# HIVE_SIGHT_POWER.net
KiCad netlist of a schematic drawn in Altium Designer
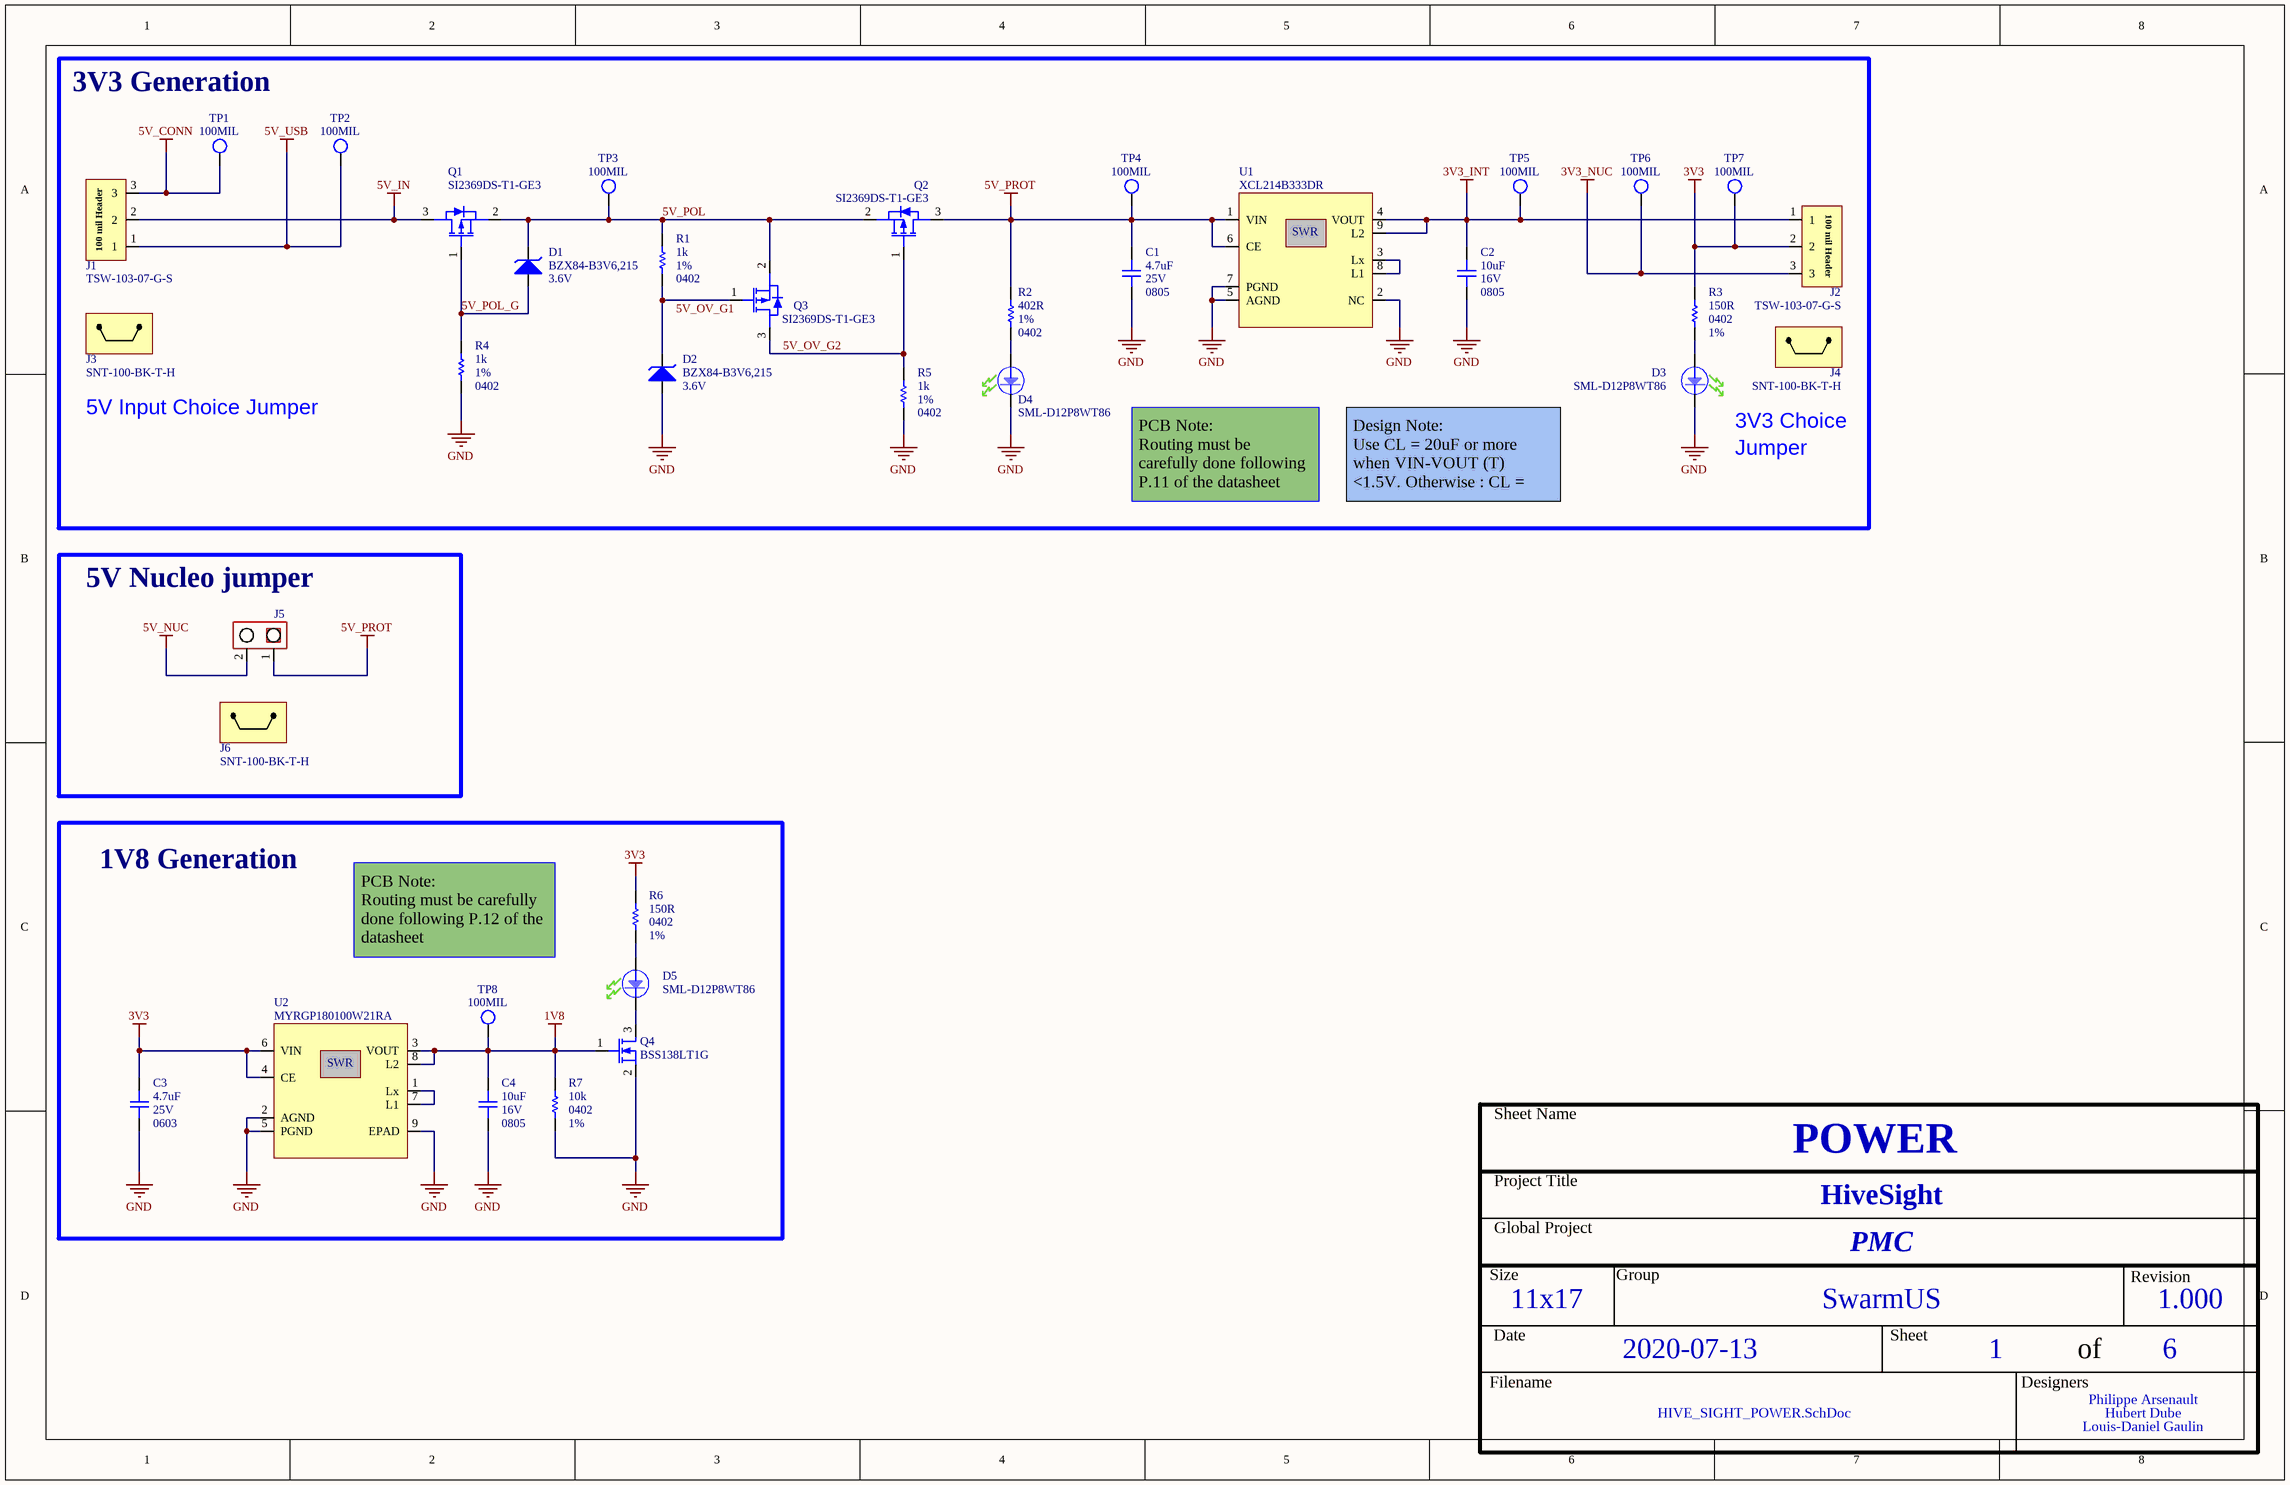
[diagram p0: HIVE_SIGHT_POWER.SchDoc]

(export (version "E")
  (design (tool "Eeschema 10.0.6"))
  (components
    (comp (ref "C1")
      (value "4.7uF")
      (footprint "CAP_CER_0805")
      (description "CAP - CER 4.7UF 10% 25V X7R - 0805")
      (fields
        (field (name "TOLERANCE") "10%")
        (field (name "PACKAGE") "0805")
        (field (name "VOLTAGE RATING") "25V")
        (field (name "Comment") "C2012X7R1E475K125AE")
        (field (name "CREATEDBY/DATE") "Keven Deslandes - 2018/11/09")
        (field (name "VERIFIEDBY") "Nicolas Roy - 2018/12/11")
      )
      (libsource (lib "GRAMS_MASTER_LIB") (part "CAP_CER_C2012X7R1E475K125AE"))
    )
    (comp (ref "C2")
      (value "10uF")
      (footprint "CAP_CER_0805")
      (description "CAP - CER 10UF 10% 16V X5R - 0805")
      (fields
        (field (name "TOLERANCE") "10%")
        (field (name "PACKAGE") "0805")
        (field (name "VOLTAGE RATING") "16V")
        (field (name "Comment") "GRM21BR61C106KE15K")
        (field (name "CREATEDBY/DATE") "Caroline Paulin / 8 août 2018")
        (field (name "VERIFIEDBY") "Nicolas V. (2019-01-22)")
      )
      (libsource (lib "GRAMS_MASTER_LIB") (part "CAP_CER_GRM21BR61C106KE15K"))
    )
    (comp (ref "C3")
      (value "4.7uF")
      (footprint "CAP_CER_0603")
      (description "CAP - CER 4.7µF 20% 25V X5R - 0603")
      (fields
        (field (name "TOLERANCE") "20%")
        (field (name "PACKAGE") "0603")
        (field (name "VOLTAGE RATING") "25V")
        (field (name "Comment") "CL10A475MA8NQNC")
        (field (name "CREATEDBY/DATE") "Nicolas Roy 2018-11-21")
        (field (name "VERIFIEDBY") "Nicolas V. (2019-01-22)")
      )
      (libsource (lib "GRAMS_MASTER_LIB") (part "CAP_CER_CL10A475MA8NQNC"))
    )
    (comp (ref "C4")
      (value "10uF")
      (footprint "CAP_CER_0805")
      (description "CAP - CER 10UF 10% 16V X5R - 0805")
      (fields
        (field (name "TOLERANCE") "10%")
        (field (name "PACKAGE") "0805")
        (field (name "VOLTAGE RATING") "16V")
        (field (name "Comment") "GRM21BR61C106KE15K")
        (field (name "CREATEDBY/DATE") "Caroline Paulin / 8 août 2018")
        (field (name "VERIFIEDBY") "Nicolas V. (2019-01-22)")
      )
      (libsource (lib "GRAMS_MASTER_LIB") (part "CAP_CER_GRM21BR61C106KE15K"))
    )
    (comp (ref "D1")
      (value "BZX84-B3V6,215")
      (footprint "DIO_ZENER_BZX84-B3V6,215")
      (description "DIO - ZENER 3.6V 250mW - SOT-23")
      (fields
        (field (name "TOLERANCE") "2%")
        (field (name "ALTIUM_VALUE") "3.6V")
        (field (name "CREATEDBY/DATE") "Louis-Daniel Gaulin / 30-07-2020")
        (field (name "VERIFIEDBY") "Philippe Arsenault/2020-11-06")
      )
      (libsource (lib "SWARMUS_LIB") (part "DIO_ZENER_BZX84-B3V6,215"))
    )
    (comp (ref "D2")
      (value "BZX84-B3V6,215")
      (footprint "DIO_ZENER_BZX84-B3V6,215")
      (description "DIO - ZENER 3.6V 250mW - SOT-23")
      (fields
        (field (name "TOLERANCE") "2%")
        (field (name "ALTIUM_VALUE") "3.6V")
        (field (name "CREATEDBY/DATE") "Louis-Daniel Gaulin / 30-07-2020")
        (field (name "VERIFIEDBY") "Philippe Arsenault/2020-11-06")
      )
      (libsource (lib "SWARMUS_LIB") (part "DIO_ZENER_BZX84-B3V6,215"))
    )
    (comp (ref "D3")
      (value "SML-D12P8WT86")
      (footprint "GRAMS_MASTER_LIB_PCB:LED_SML-D12P8WT86")
      (description "LED - GREEN DIFFUSED 0603 SMD - 0603")
      (fields
        (field (name "CREATEDBY/DATE") "Keven Deslandes - 2018/11/21")
        (field (name "VERIFIEDBY") "Caroline Paulin - 13 février 2019")
      )
      (libsource (lib "GRAMS_MASTER_LIB_SCH") (part "LED_SML-D12P8WT86"))
    )
    (comp (ref "D4")
      (value "SML-D12P8WT86")
      (footprint "GRAMS_MASTER_LIB_PCB:LED_SML-D12P8WT86")
      (description "LED - GREEN DIFFUSED 0603 SMD - 0603")
      (fields
        (field (name "CREATEDBY/DATE") "Keven Deslandes - 2018/11/21")
        (field (name "VERIFIEDBY") "Caroline Paulin - 13 février 2019")
      )
      (libsource (lib "GRAMS_MASTER_LIB_SCH") (part "LED_SML-D12P8WT86"))
    )
    (comp (ref "D5")
      (value "SML-D12P8WT86")
      (footprint "GRAMS_MASTER_LIB_PCB:LED_SML-D12P8WT86")
      (description "LED - GREEN DIFFUSED 0603 SMD - 0603")
      (fields
        (field (name "CREATEDBY/DATE") "Keven Deslandes - 2018/11/21")
        (field (name "VERIFIEDBY") "Caroline Paulin - 13 février 2019")
      )
      (libsource (lib "GRAMS_MASTER_LIB_SCH") (part "LED_SML-D12P8WT86"))
    )
    (comp (ref "J1")
      (value "TSW-103-07-G-S")
      (footprint "CON_HDR_TSW-103-07-G-S")
      (description "CON - HDR 100 MIL 3 POS - TH")
      (fields
        (field (name "CREATEDBY/DATE") "Jonathan Bouchard")
        (field (name "VERIFIEDBY") "Arnaud Samson 16-07-18")
      )
      (libsource (lib "") (part "CON_HDR_TSW-103-07-G-S_1"))
    )
    (comp (ref "J2")
      (value "TSW-103-07-G-S")
      (footprint "CON_HDR_TSW-103-07-G-S")
      (description "CON - HDR 100 MIL 3 POS - TH")
      (fields
        (field (name "CREATEDBY/DATE") "Jonathan Bouchard")
        (field (name "VERIFIEDBY") "Arnaud Samson 16-07-18")
      )
      (libsource (lib "GRAMS_MASTER_LIB") (part "CON_HDR_TSW-103-07-G-S"))
    )
    (comp (ref "J3")
      (value "SNT-100-BK-T-H")
      (footprint "CON_JMP_SNT-100-BK-T-H")
      (description "CON - CONN SHUNT - MEC")
      (fields
        (field (name "CREATEDBY/DATE") "Arnaud Samson - 09/07/18")
        (field (name "VERIFIEDBY") "Jonathan Bouchard 2018-07-12")
      )
      (libsource (lib "GRAMS_MASTER_LIB") (part "CON_JMP_SNT-100-BK-T-H"))
    )
    (comp (ref "J4")
      (value "SNT-100-BK-T-H")
      (footprint "CON_JMP_SNT-100-BK-T-H")
      (description "CON - CONN SHUNT - MEC")
      (fields
        (field (name "CREATEDBY/DATE") "Arnaud Samson - 09/07/18")
        (field (name "VERIFIEDBY") "Jonathan Bouchard 2018-07-12")
      )
      (libsource (lib "GRAMS_MASTER_LIB") (part "CON_JMP_SNT-100-BK-T-H"))
    )
    (comp (ref "J5")
      (value "CON_HDR_1x2")
      (footprint "CON_HDR_1X2")
      (description "CON - Header 1x2 pins 100 mil -TH")
      (fields
        (field (name "CREATEDBY/DATE") "Nicolas Roy/2 dec 2016")
        (field (name "VERIFIEDBY") "Caroline Paulin / 10 juillet 2018")
      )
      (libsource (lib "GRAMS_MASTER_LIB") (part "CON_HDR_1X2"))
    )
    (comp (ref "J6")
      (value "SNT-100-BK-T-H")
      (footprint "CON_JMP_SNT-100-BK-T-H")
      (description "CON - CONN SHUNT - MEC")
      (fields
        (field (name "CREATEDBY/DATE") "Arnaud Samson - 09/07/18")
        (field (name "VERIFIEDBY") "Jonathan Bouchard 2018-07-12")
      )
      (libsource (lib "GRAMS_MASTER_LIB") (part "CON_JMP_SNT-100-BK-T-H"))
    )
    (comp (ref "Q1")
      (value "SI2369DS-T1-GE3")
      (footprint "TRX_PMOS_SI2369DS-T1-GE3")
      (description "TRX - PMOS 30V 7.6A - SOT−23")
      (fields
        (field (name "CREATEDBY/DATE") "Louis-Daniel Gaulin / 30-07-2020")
        (field (name "VERIFIEDBY") "Philippe Arsenault/2020-11-06")
      )
      (libsource (lib "SWARMUS_LIB") (part "TRX_PMOS_SI2369DS-T1-GE3"))
    )
    (comp (ref "Q2")
      (value "SI2369DS-T1-GE3")
      (footprint "TRX_PMOS_SI2369DS-T1-GE3")
      (description "TRX - PMOS 30V 7.6A - SOT−23")
      (fields
        (field (name "CREATEDBY/DATE") "Louis-Daniel Gaulin / 30-07-2020")
        (field (name "VERIFIEDBY") "Philippe Arsenault/2020-11-06")
      )
      (libsource (lib "SWARMUS_LIB") (part "TRX_PMOS_SI2369DS-T1-GE3"))
    )
    (comp (ref "Q3")
      (value "SI2369DS-T1-GE3")
      (footprint "TRX_PMOS_SI2369DS-T1-GE3")
      (description "TRX - PMOS 30V 7.6A - SOT−23")
      (fields
        (field (name "CREATEDBY/DATE") "Louis-Daniel Gaulin / 30-07-2020")
        (field (name "VERIFIEDBY") "Philippe Arsenault/2020-11-06")
      )
      (libsource (lib "SWARMUS_LIB") (part "TRX_PMOS_SI2369DS-T1-GE3"))
    )
    (comp (ref "Q4")
      (value "BSS138LT1G")
      (footprint "TRX_NMOS_BSS138LT1G")
      (description "TRX - NMOS - 50V 200MA - SOT−23-3")
      (fields
        (field (name "CREATEDBY/DATE") "Joel Lemay 2018-06-15")
        (field (name "VERIFIEDBY") "Caroline Paulin - 6 sept 2018")
      )
      (libsource (lib "GRAMS_MASTER_LIB") (part "TRX_NMOS_BSS138LT1G"))
    )
    (comp (ref "R1")
      (value "1k")
      (footprint "GRAMS_MASTER_LIB_PCB:RES_0402")
      (description "RES - 1K OHM 1% 1/16W - 0402")
      (fields
        (field (name "TOLERANCE") "1%")
        (field (name "PACKAGE") "0402")
        (field (name "Comment") "RC0402FR-071KL")
        (field (name "CREATEDBY/DATE") "Jonathan Bouchard 2018-07-05")
        (field (name "VERIFIEDBY") "Arnaud Samson 16-07-18")
      )
      (libsource (lib "GRAMS_MASTER_LIB_SCH") (part "RES_RC0402FR-071KL"))
    )
    (comp (ref "R2")
      (value "402R")
      (footprint "RES_0402")
      (description "RES - 402R 1% 1/10W - 0402")
      (fields
        (field (name "TOLERANCE") "1%")
        (field (name "PACKAGE") "0402")
        (field (name "Comment") "ERJ-2RKF4020X")
        (field (name "CREATEDBY/DATE") "Keven Deslandes 2018-09-20")
        (field (name "VERIFIEDBY") "Caroline Paulin - 18/12/2018")
      )
      (libsource (lib "GRAMS_MASTER_LIB") (part "RES_ERJ-2RKF4020X"))
    )
    (comp (ref "R3")
      (value "150R")
      (footprint "RES_0402")
      (description "RES - 150R 1% 1/16W - 0402")
      (fields
        (field (name "TOLERANCE") "1%")
        (field (name "PACKAGE") "0402")
        (field (name "Comment") "RC0402FR-07150RL")
        (field (name "CREATEDBY/DATE") "Jonathan Bouchard 2019-03-25")
        (field (name "VERIFIEDBY") "Nicolas V. (2019-05-02)")
      )
      (libsource (lib "GRAMS_MASTER_LIB") (part "RES_RC0402FR-07150RL"))
    )
    (comp (ref "R4")
      (value "1k")
      (footprint "GRAMS_MASTER_LIB_PCB:RES_0402")
      (description "RES - 1K OHM 1% 1/16W - 0402")
      (fields
        (field (name "TOLERANCE") "1%")
        (field (name "PACKAGE") "0402")
        (field (name "Comment") "RC0402FR-071KL")
        (field (name "CREATEDBY/DATE") "Jonathan Bouchard 2018-07-05")
        (field (name "VERIFIEDBY") "Arnaud Samson 16-07-18")
      )
      (libsource (lib "GRAMS_MASTER_LIB_SCH") (part "RES_RC0402FR-071KL"))
    )
    (comp (ref "R5")
      (value "1k")
      (footprint "GRAMS_MASTER_LIB_PCB:RES_0402")
      (description "RES - 1K OHM 1% 1/16W - 0402")
      (fields
        (field (name "TOLERANCE") "1%")
        (field (name "PACKAGE") "0402")
        (field (name "Comment") "RC0402FR-071KL")
        (field (name "CREATEDBY/DATE") "Jonathan Bouchard 2018-07-05")
        (field (name "VERIFIEDBY") "Arnaud Samson 16-07-18")
      )
      (libsource (lib "GRAMS_MASTER_LIB_SCH") (part "RES_RC0402FR-071KL"))
    )
    (comp (ref "R6")
      (value "150R")
      (footprint "RES_0402")
      (description "RES - 150R 1% 1/16W - 0402")
      (fields
        (field (name "TOLERANCE") "1%")
        (field (name "PACKAGE") "0402")
        (field (name "Comment") "RC0402FR-07150RL")
        (field (name "CREATEDBY/DATE") "Jonathan Bouchard 2019-03-25")
        (field (name "VERIFIEDBY") "Nicolas V. (2019-05-02)")
      )
      (libsource (lib "GRAMS_MASTER_LIB") (part "RES_RC0402FR-07150RL"))
    )
    (comp (ref "R7")
      (value "10k")
      (footprint "GRAMS_MASTER_LIB_PCB:RES_0402")
      (description "RES - 10K OHMS 1% 1/16W - 0402")
      (fields
        (field (name "TOLERANCE") "1%")
        (field (name "PACKAGE") "0402")
        (field (name "Comment") "RC0402FR-0710KL")
        (field (name "CREATEDBY/DATE") "Nicolas V. (2018-11-20)")
        (field (name "VERIFIEDBY") "Nicolas V. (2018-11-20)")
      )
      (libsource (lib "GRAMS_MASTER_LIB_SCH") (part "RES_RC0402FR-0710KL"))
    )
    (comp (ref "TP1")
      (value "100MIL")
      (footprint "grams_master_lib_pcb:TPO_TH_ROUND_100MIL")
      (description "TPO - TEST POINT ROUND TH  - 100MIL")
      (fields
        (field (name "CREATEDBY/DATE") "Louis-Daniel Gaulin/ 14/01/2020")
        (field (name "VERIFIEDBY") "C.Paulin - 21/01/2020")
      )
      (libsource (lib "GRAMS_MASTER_LIB_SCH") (part "TPO_TH_ROUND_100MIL"))
    )
    (comp (ref "TP2")
      (value "100MIL")
      (footprint "grams_master_lib_pcb:TPO_TH_ROUND_100MIL")
      (description "TPO - TEST POINT ROUND TH  - 100MIL")
      (fields
        (field (name "CREATEDBY/DATE") "Louis-Daniel Gaulin/ 14/01/2020")
        (field (name "VERIFIEDBY") "C.Paulin - 21/01/2020")
      )
      (libsource (lib "GRAMS_MASTER_LIB_SCH") (part "TPO_TH_ROUND_100MIL"))
    )
    (comp (ref "TP3")
      (value "100MIL")
      (footprint "grams_master_lib_pcb:TPO_TH_ROUND_100MIL")
      (description "TPO - TEST POINT ROUND TH  - 100MIL")
      (fields
        (field (name "CREATEDBY/DATE") "Louis-Daniel Gaulin/ 14/01/2020")
        (field (name "VERIFIEDBY") "C.Paulin - 21/01/2020")
      )
      (libsource (lib "GRAMS_MASTER_LIB_SCH") (part "TPO_TH_ROUND_100MIL"))
    )
    (comp (ref "TP4")
      (value "100MIL")
      (footprint "grams_master_lib_pcb:TPO_TH_ROUND_100MIL")
      (description "TPO - TEST POINT ROUND TH  - 100MIL")
      (fields
        (field (name "CREATEDBY/DATE") "Louis-Daniel Gaulin/ 14/01/2020")
        (field (name "VERIFIEDBY") "C.Paulin - 21/01/2020")
      )
      (libsource (lib "GRAMS_MASTER_LIB_SCH") (part "TPO_TH_ROUND_100MIL"))
    )
    (comp (ref "TP5")
      (value "100MIL")
      (footprint "grams_master_lib_pcb:TPO_TH_ROUND_100MIL")
      (description "TPO - TEST POINT ROUND TH  - 100MIL")
      (fields
        (field (name "CREATEDBY/DATE") "Louis-Daniel Gaulin/ 14/01/2020")
        (field (name "VERIFIEDBY") "C.Paulin - 21/01/2020")
      )
      (libsource (lib "GRAMS_MASTER_LIB_SCH") (part "TPO_TH_ROUND_100MIL"))
    )
    (comp (ref "TP6")
      (value "100MIL")
      (footprint "grams_master_lib_pcb:TPO_TH_ROUND_100MIL")
      (description "TPO - TEST POINT ROUND TH  - 100MIL")
      (fields
        (field (name "CREATEDBY/DATE") "Louis-Daniel Gaulin/ 14/01/2020")
        (field (name "VERIFIEDBY") "C.Paulin - 21/01/2020")
      )
      (libsource (lib "GRAMS_MASTER_LIB_SCH") (part "TPO_TH_ROUND_100MIL"))
    )
    (comp (ref "TP7")
      (value "100MIL")
      (footprint "grams_master_lib_pcb:TPO_TH_ROUND_100MIL")
      (description "TPO - TEST POINT ROUND TH  - 100MIL")
      (fields
        (field (name "CREATEDBY/DATE") "Louis-Daniel Gaulin/ 14/01/2020")
        (field (name "VERIFIEDBY") "C.Paulin - 21/01/2020")
      )
      (libsource (lib "GRAMS_MASTER_LIB_SCH") (part "TPO_TH_ROUND_100MIL"))
    )
    (comp (ref "TP8")
      (value "100MIL")
      (footprint "grams_master_lib_pcb:TPO_TH_ROUND_100MIL")
      (description "TPO - TEST POINT ROUND TH  - 100MIL")
      (fields
        (field (name "CREATEDBY/DATE") "Louis-Daniel Gaulin/ 14/01/2020")
        (field (name "VERIFIEDBY") "C.Paulin - 21/01/2020")
      )
      (libsource (lib "GRAMS_MASTER_LIB_SCH") (part "TPO_TH_ROUND_100MIL"))
    )
    (comp (ref "U1")
      (value "XCL214B333DR")
      (footprint "REG_SWR_XCL214B333DR")
      (description "REG_DC DC CONVERTER 3.3V 5W_9-PowerTFQFN")
      (fields
        (field (name "CREATEDBY/DATE") "Louis-Daniel Gaulin / 21-07-2020")
        (field (name "VERIFIEDBY") "Philippe Arsenault/2020-11-06")
      )
      (libsource (lib "SWARMUS_LIB") (part "REG_SWR_XCL214B333DR"))
    )
    (comp (ref "U2")
      (value "MYRGP180100W21RA")
      (footprint "REG_SWR_MYRGP180100W21RA")
      (description "REG_DC DC CONVERTER 1.8V 1.8W_8-PowerTDFN")
      (fields
        (field (name "CREATEDBY/DATE") "Louis-Daniel Gaulin / 21-07-2020")
        (field (name "VERIFIEDBY") "Philippe Arsenault/2020-11-06")
      )
      (libsource (lib "SWARMUS_LIB") (part "REG_SWR_MYRGP180100W21RA"))
    )
  )
  (nets
    (net (code "1") (name "/5V_OV_G1") (class "Default")
      (node (ref "D2") (pin "3") (pinfunction "K_3") (pintype "passive"))
      (node (ref "Q3") (pin "1") (pinfunction "G_1") (pintype "passive"))
      (node (ref "R1") (pin "2") (pinfunction "2_2") (pintype "passive"))
    )
    (net (code "2") (name "/5V_OV_G2") (class "Default")
      (node (ref "Q2") (pin "1") (pinfunction "G_1") (pintype "passive"))
      (node (ref "Q3") (pin "3") (pinfunction "D_3") (pintype "passive"))
      (node (ref "R5") (pin "1") (pinfunction "1_1") (pintype "passive"))
    )
    (net (code "3") (name "/5V_POL") (class "Default")
      (node (ref "D1") (pin "3") (pinfunction "K_3") (pintype "passive"))
      (node (ref "Q1") (pin "2") (pinfunction "S_2") (pintype "passive"))
      (node (ref "Q2") (pin "2") (pinfunction "S_2") (pintype "passive"))
      (node (ref "Q3") (pin "2") (pinfunction "S_2") (pintype "passive"))
      (node (ref "R1") (pin "1") (pinfunction "1_1") (pintype "passive"))
      (node (ref "TP3") (pin "1") (pinfunction "1_1") (pintype "passive"))
    )
    (net (code "4") (name "/5V_POL_G") (class "Default")
      (node (ref "D1") (pin "1") (pinfunction "A_1") (pintype "passive"))
      (node (ref "Q1") (pin "1") (pinfunction "G_1") (pintype "passive"))
      (node (ref "R4") (pin "1") (pinfunction "1_1") (pintype "passive"))
    )
    (net (code "5") (name "1V8") (class "Default")
      (node (ref "C4") (pin "2") (pinfunction "2_2") (pintype "passive"))
      (node (ref "Q4") (pin "1") (pinfunction "G_1") (pintype "passive"))
      (node (ref "R7") (pin "1") (pinfunction "1_1") (pintype "passive"))
      (node (ref "TP8") (pin "1") (pinfunction "1_1") (pintype "passive"))
      (node (ref "U2") (pin "3") (pinfunction "VOUT_3") (pintype "passive"))
      (node (ref "U2") (pin "8") (pinfunction "L2_8") (pintype "passive"))
    )
    (net (code "6") (name "3V3") (class "Default")
      (node (ref "C3") (pin "2") (pinfunction "2_2") (pintype "passive"))
      (node (ref "J2") (pin "2") (pinfunction "2_2") (pintype "passive"))
      (node (ref "R3") (pin "1") (pinfunction "1_1") (pintype "passive"))
      (node (ref "R6") (pin "1") (pinfunction "1_1") (pintype "passive"))
      (node (ref "TP7") (pin "1") (pinfunction "1_1") (pintype "passive"))
      (node (ref "U2") (pin "4") (pinfunction "CE_4") (pintype "passive"))
      (node (ref "U2") (pin "6") (pinfunction "VIN_6") (pintype "passive"))
    )
    (net (code "7") (name "3V3_INT") (class "Default")
      (node (ref "C2") (pin "2") (pinfunction "2_2") (pintype "passive"))
      (node (ref "J2") (pin "1") (pinfunction "1_1") (pintype "passive"))
      (node (ref "TP5") (pin "1") (pinfunction "1_1") (pintype "passive"))
      (node (ref "U1") (pin "4") (pinfunction "VOUT_4") (pintype "passive"))
      (node (ref "U1") (pin "9") (pinfunction "L2_9") (pintype "passive"))
    )
    (net (code "8") (name "3V3_NUC") (class "Default")
      (node (ref "J2") (pin "3") (pinfunction "3_3") (pintype "passive"))
      (node (ref "TP6") (pin "1") (pinfunction "1_1") (pintype "passive"))
    )
    (net (code "9") (name "5V_CONN") (class "Default")
      (node (ref "J1") (pin "3") (pinfunction "3_3") (pintype "passive"))
      (node (ref "TP1") (pin "1") (pinfunction "1_1") (pintype "passive"))
    )
    (net (code "10") (name "5V_IN") (class "Default")
      (node (ref "J1") (pin "2") (pinfunction "2_2") (pintype "passive"))
      (node (ref "Q1") (pin "3") (pinfunction "D_3") (pintype "passive"))
    )
    (net (code "11") (name "5V_NUC") (class "Default")
      (node (ref "J5") (pin "2") (pinfunction "2_2") (pintype "passive"))
    )
    (net (code "12") (name "5V_PROT") (class "Default")
      (node (ref "C1") (pin "2") (pinfunction "2_2") (pintype "passive"))
      (node (ref "J5") (pin "1") (pinfunction "1_1") (pintype "passive"))
      (node (ref "Q2") (pin "3") (pinfunction "D_3") (pintype "passive"))
      (node (ref "R2") (pin "2") (pinfunction "2_2") (pintype "passive"))
      (node (ref "TP4") (pin "1") (pinfunction "1_1") (pintype "passive"))
      (node (ref "U1") (pin "1") (pinfunction "VIN_1") (pintype "passive"))
      (node (ref "U1") (pin "6") (pinfunction "CE_6") (pintype "passive"))
    )
    (net (code "13") (name "5V_USB") (class "Default")
      (node (ref "J1") (pin "1") (pinfunction "1_1") (pintype "passive"))
      (node (ref "TP2") (pin "1") (pinfunction "1_1") (pintype "passive"))
    )
    (net (code "14") (name "GND") (class "Default")
      (node (ref "C1") (pin "1") (pinfunction "1_1") (pintype "passive"))
      (node (ref "C2") (pin "1") (pinfunction "1_1") (pintype "passive"))
      (node (ref "C3") (pin "1") (pinfunction "1_1") (pintype "passive"))
      (node (ref "C4") (pin "1") (pinfunction "1_1") (pintype "passive"))
      (node (ref "D2") (pin "1") (pinfunction "A_1") (pintype "passive"))
      (node (ref "D3") (pin "K") (pinfunction "K_K") (pintype "passive"))
      (node (ref "D4") (pin "K") (pinfunction "K_K") (pintype "passive"))
      (node (ref "Q4") (pin "2") (pinfunction "S_2") (pintype "passive"))
      (node (ref "R4") (pin "2") (pinfunction "2_2") (pintype "passive"))
      (node (ref "R5") (pin "2") (pinfunction "2_2") (pintype "passive"))
      (node (ref "R7") (pin "2") (pinfunction "2_2") (pintype "passive"))
      (node (ref "U1") (pin "2") (pinfunction "NC_2") (pintype "passive"))
      (node (ref "U1") (pin "5") (pinfunction "AGND_5") (pintype "passive"))
      (node (ref "U1") (pin "7") (pinfunction "PGND_7") (pintype "passive"))
      (node (ref "U2") (pin "2") (pinfunction "AGND_2") (pintype "passive"))
      (node (ref "U2") (pin "5") (pinfunction "PGND_5") (pintype "passive"))
      (node (ref "U2") (pin "9") (pinfunction "EPAD_9") (pintype "passive"))
    )
    (net (code "15") (name "Net-(D3-PadA)") (class "Default")
      (node (ref "D3") (pin "A") (pinfunction "A_A") (pintype "passive"))
      (node (ref "R3") (pin "2") (pinfunction "2_2") (pintype "passive"))
    )
    (net (code "16") (name "Net-(D4-PadA)") (class "Default")
      (node (ref "D4") (pin "A") (pinfunction "A_A") (pintype "passive"))
      (node (ref "R2") (pin "1") (pinfunction "1_1") (pintype "passive"))
    )
    (net (code "17") (name "Net-(D5-PadA)") (class "Default")
      (node (ref "D5") (pin "A") (pinfunction "A_A") (pintype "passive"))
      (node (ref "R6") (pin "2") (pinfunction "2_2") (pintype "passive"))
    )
    (net (code "18") (name "Net-(Q4-D)") (class "Default")
      (node (ref "D5") (pin "K") (pinfunction "K_K") (pintype "passive"))
      (node (ref "Q4") (pin "3") (pinfunction "D_3") (pintype "passive"))
    )
    (net (code "19") (name "Net-(U1-L1)") (class "Default")
      (node (ref "U1") (pin "3") (pinfunction "Lx_3") (pintype "passive"))
      (node (ref "U1") (pin "8") (pinfunction "L1_8") (pintype "passive"))
    )
    (net (code "20") (name "Net-(U2-L1)") (class "Default")
      (node (ref "U2") (pin "1") (pinfunction "Lx_1") (pintype "passive"))
      (node (ref "U2") (pin "7") (pinfunction "L1_7") (pintype "passive"))
    )
    (net (code "21") (name "unconnected-(D1-NC-Pad2)") (class "Default")
      (node (ref "D1") (pin "2") (pinfunction "NC_2") (pintype "passive"))
    )
    (net (code "22") (name "unconnected-(D2-NC-Pad2)") (class "Default")
      (node (ref "D2") (pin "2") (pinfunction "NC_2") (pintype "passive"))
    )
  )
)
